# eda.net
KiCad netlist of a schematic drawn in EasyEDA Pro
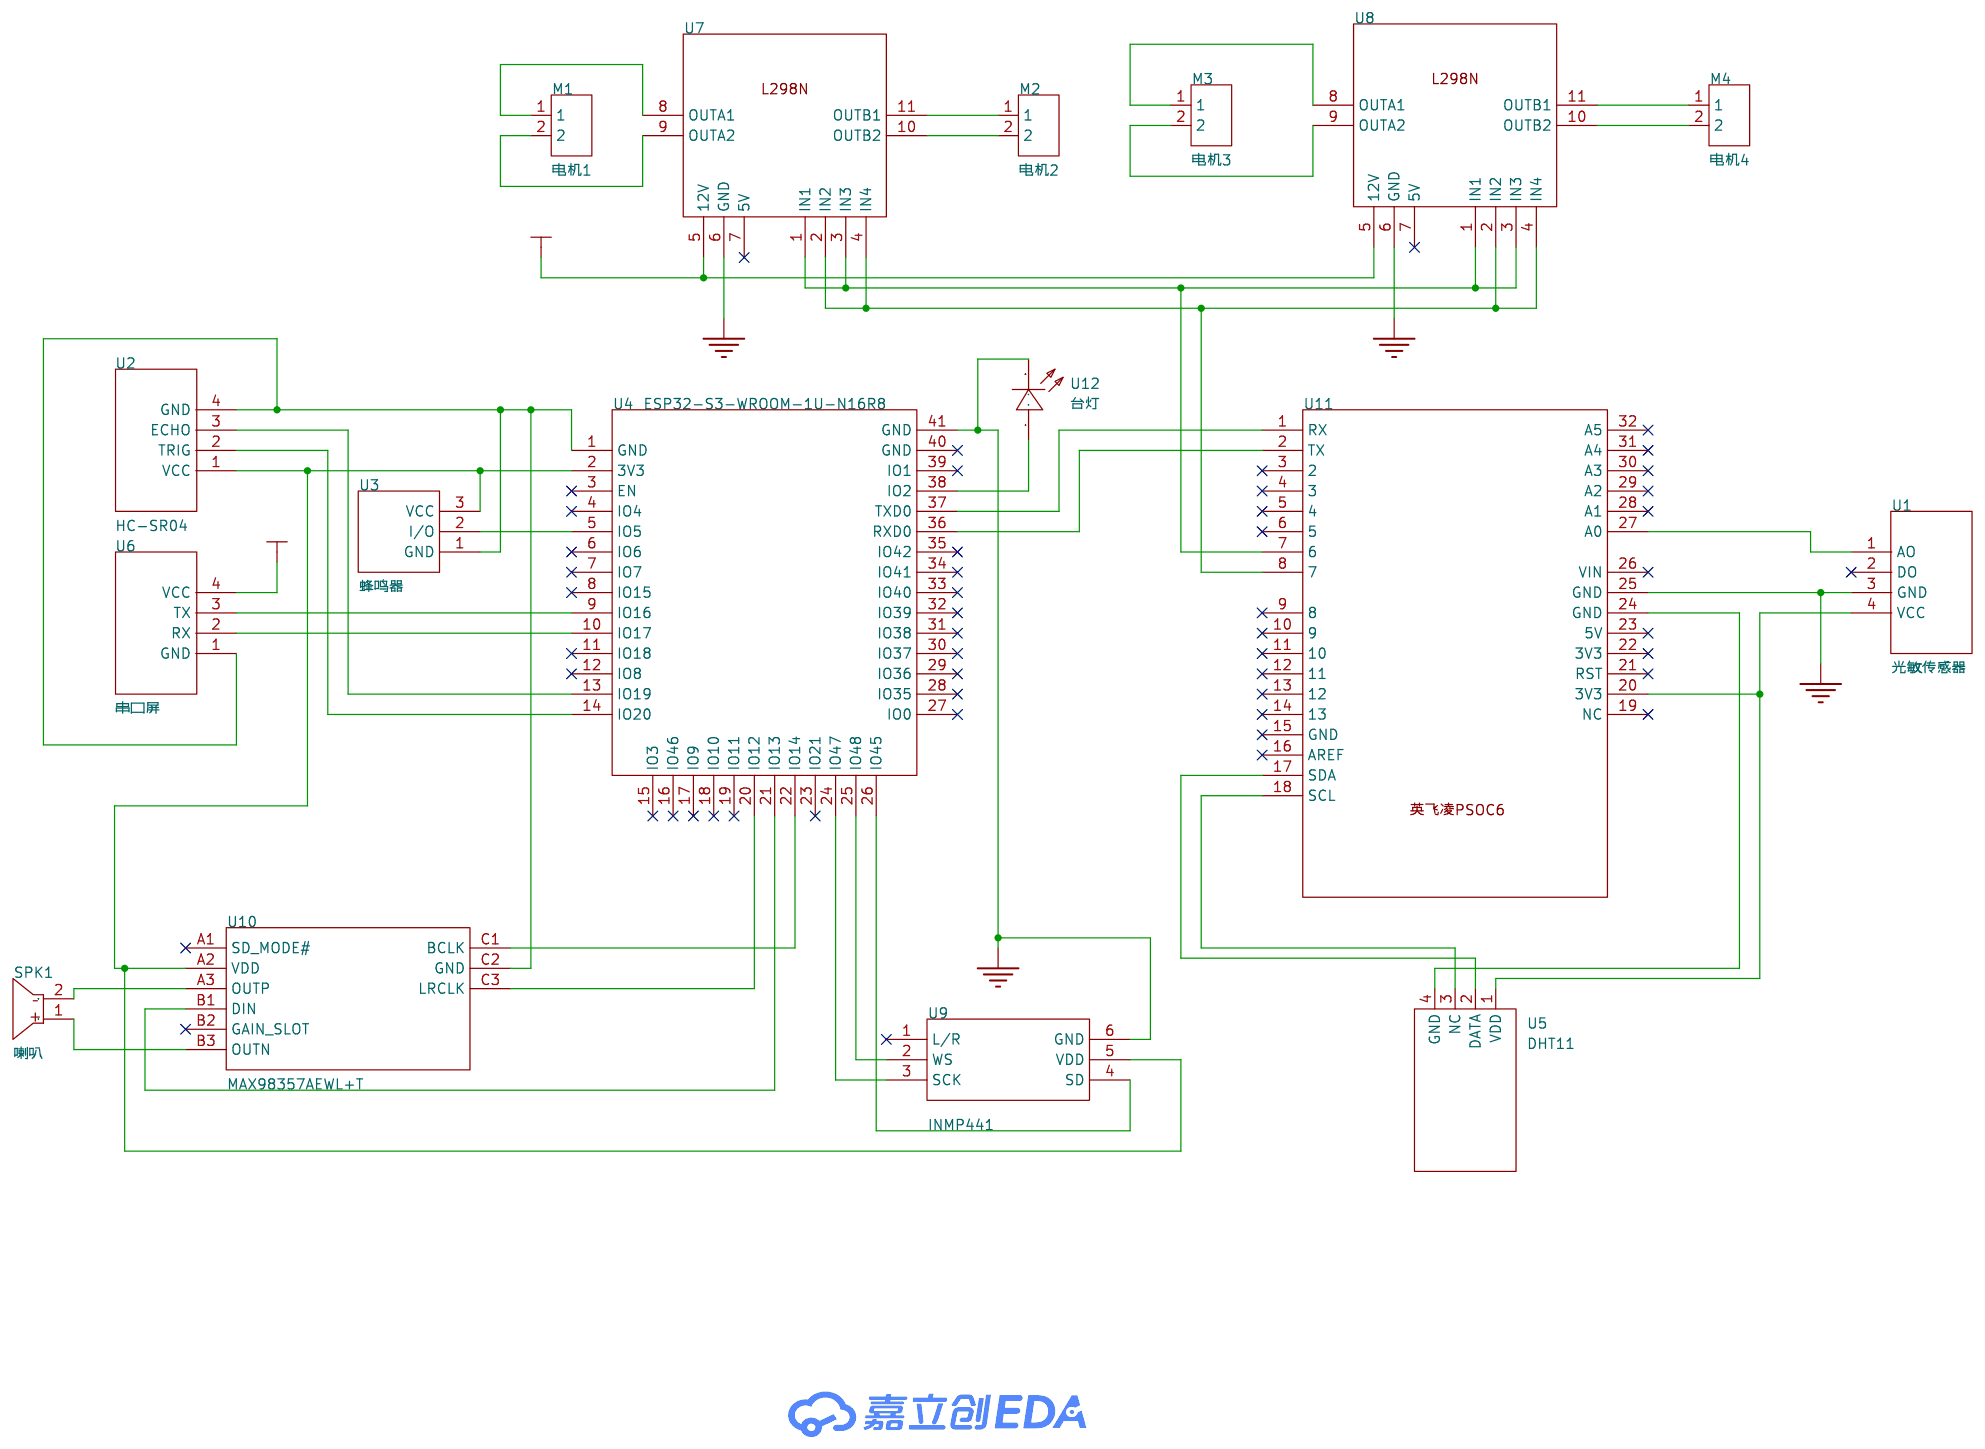
[diagram p0: schematic sheet]

(export (version "E")
  (design (tool "Eeschema 10.0.6"))
  (components
    (comp (ref "M1")
      (value "电机1")
      (footprint "easyedapro:CONN-TH_KF2510-2A")
      (libsource (lib "easyedapro") (part "外接电机-KF2510直针 两个针间距2.54MM"))
    )
    (comp (ref "M2")
      (value "电机2")
      (footprint "easyedapro:CONN-TH_KF2510-2A")
      (libsource (lib "easyedapro") (part "外接电机-KF2510直针 两个针间距2.54MM"))
    )
    (comp (ref "M3")
      (value "电机3")
      (footprint "easyedapro:CONN-TH_KF2510-2A")
      (libsource (lib "easyedapro") (part "外接电机-KF2510直针 两个针间距2.54MM"))
    )
    (comp (ref "M4")
      (value "电机4")
      (footprint "easyedapro:CONN-TH_KF2510-2A")
      (libsource (lib "easyedapro") (part "外接电机-KF2510直针 两个针间距2.54MM"))
    )
    (comp (ref "SPK1")
      (value "喇叭")
      (footprint "easyedapro:BEEP-TH_BD15.0-P10.20-D1.2")
      (description "插针")
      (fields (field (name "Manufacturer") "FUET(福声科技)"))
      (libsource (lib "easyedapro") (part "FS1508MB0810-H8.0"))
    )
    (comp (ref "U1") (value "光敏传感器") (libsource (lib "easyedapro") (part "光敏传感器")))
    (comp (ref "U2") (value "HC-SR04") (libsource (lib "easyedapro") (part "超声波传感器")))
    (comp (ref "U3") (value "蜂鸣器") (libsource (lib "easyedapro") (part "蜂鸣器模块")))
    (comp (ref "U4")
      (value "ESP32-S3-WROOM-1U-N16R8")
      (footprint "easyedapro:WIRELM-SMD_ESP32-S3-WROOM-1U")
      (fields (field (name "Manufacturer") "ESPRESSIF(乐鑫)"))
      (libsource (lib "easyedapro") (part "ESP32-S3-WROOM-1U-N16R8"))
    )
    (comp (ref "U5")
      (value "DHT11")
      (footprint "easyedapro:SENSOR-TH_DHT11")
      (description "新款电容式数字温湿度传感器,老款已停产16.1x12.6x5.8mm")
      (fields (field (name "Manufacturer") "广州奥松"))
      (libsource (lib "easyedapro") (part "DHT11"))
    )
    (comp (ref "U6") (value "串口屏") (libsource (lib "easyedapro") (part "陶晶驰串口屏")))
    (comp (ref "U7") (value "~") (libsource (lib "easyedapro") (part "L298N")))
    (comp (ref "U8") (value "~") (libsource (lib "easyedapro") (part "L298N")))
    (comp (ref "U9") (value "INMP441") (libsource (lib "easyedapro") (part "INMP411")))
    (comp (ref "U10")
      (value "MAX98357AEWL+T")
      (footprint "easyedapro:WLP-9_L1.4-W1.3-P0.40-R3-C3-BR")
      (description "功放类型:-;扬声器通道数:单声道；双声道;输出功率:-;静态电流(Iq):-;")
      (fields (field (name "Manufacturer") "ADI(亚德诺)/MAXIM(美信)"))
      (libsource (lib "easyedapro") (part "MAX98357AEWL+T"))
    )
    (comp (ref "U11") (value "~") (libsource (lib "easyedapro") (part "PSOC6")))
    (comp (ref "U12")
      (value "台灯")
      (footprint "easyedapro:LED0603-R-RD_BLUE")
      (libsource (lib "easyedapro") (part "LED灯,0603,蓝色"))
    )
  )
  (nets
    (net (code "1") (name "5V") (class "Default")
      (node (ref "U6") (pin "4") (pinfunction "VCC_4") (pintype "input"))
    )
    (net (code "2") (name "12V") (class "Default")
      (node (ref "U7") (pin "5") (pinfunction "12V_5") (pintype "input"))
      (node (ref "U8") (pin "5") (pinfunction "12V_5") (pintype "input"))
    )
    (net (code "3") (name "GND") (class "Default")
      (node (ref "U1") (pin "3") (pinfunction "GND_3") (pintype "input"))
      (node (ref "U11") (pin "25") (pinfunction "GND_25") (pintype "input"))
      (node (ref "U12") (pin "2") (pinfunction "K_2") (pintype "unspecified"))
      (node (ref "U4") (pin "41") (pinfunction "GND_41") (pintype "unspecified"))
      (node (ref "U7") (pin "6") (pinfunction "GND_6") (pintype "input"))
      (node (ref "U8") (pin "6") (pinfunction "GND_6") (pintype "input"))
      (node (ref "U9") (pin "6") (pinfunction "GND_6") (pintype "input"))
    )
    (net (code "4") (name "Net-(U1-AO)") (class "Default")
      (node (ref "U1") (pin "1") (pinfunction "AO_1") (pintype "input"))
      (node (ref "U11") (pin "27") (pinfunction "A0_27") (pintype "input"))
    )
    (net (code "5") (name "Net-(U1-VCC)") (class "Default")
      (node (ref "U1") (pin "4") (pinfunction "VCC_4") (pintype "input"))
      (node (ref "U11") (pin "20") (pinfunction "3V3_20") (pintype "input"))
      (node (ref "U5") (pin "1") (pinfunction "VDD_1") (pintype "unspecified"))
    )
    (net (code "6") (name "Net-(U2-ECHO)") (class "Default")
      (node (ref "U2") (pin "3") (pinfunction "ECHO_3") (pintype "input"))
      (node (ref "U4") (pin "13") (pinfunction "IO19_13") (pintype "unspecified"))
    )
    (net (code "7") (name "Net-(U2-TRIG)") (class "Default")
      (node (ref "U2") (pin "2") (pinfunction "TRIG_2") (pintype "input"))
      (node (ref "U4") (pin "14") (pinfunction "IO20_14") (pintype "unspecified"))
    )
    (net (code "8") (name "Net-(U3-I{slash}O)") (class "Default")
      (node (ref "U3") (pin "2") (pinfunction "I/O_2") (pintype "input"))
      (node (ref "U4") (pin "5") (pinfunction "IO5_5") (pintype "unspecified"))
    )
    (net (code "9") (name "Net-(U4-IO16)") (class "Default")
      (node (ref "U4") (pin "9") (pinfunction "IO16_9") (pintype "unspecified"))
      (node (ref "U6") (pin "3") (pinfunction "TX_3") (pintype "input"))
    )
    (net (code "10") (name "Net-(U4-IO17)") (class "Default")
      (node (ref "U4") (pin "10") (pinfunction "IO17_10") (pintype "unspecified"))
      (node (ref "U6") (pin "2") (pinfunction "RX_2") (pintype "input"))
    )
    (net (code "11") (name "Net-(U4-IO45)") (class "Default")
      (node (ref "U4") (pin "26") (pinfunction "IO45_26") (pintype "unspecified"))
      (node (ref "U9") (pin "4") (pinfunction "SD_4") (pintype "input"))
    )
    (net (code "12") (name "Net-(U4-IO47)") (class "Default")
      (node (ref "U4") (pin "24") (pinfunction "IO47_24") (pintype "unspecified"))
      (node (ref "U9") (pin "3") (pinfunction "SCK_3") (pintype "input"))
    )
    (net (code "13") (name "Net-(U4-IO48)") (class "Default")
      (node (ref "U4") (pin "25") (pinfunction "IO48_25") (pintype "unspecified"))
      (node (ref "U9") (pin "2") (pinfunction "WS_2") (pintype "input"))
    )
    (net (code "14") (name "Net-(U5-GND)") (class "Default")
      (node (ref "U11") (pin "24") (pinfunction "GND_24") (pintype "input"))
      (node (ref "U5") (pin "4") (pinfunction "GND_4") (pintype "unspecified"))
    )
    (net (code "15") (name "Net-(U7-OUTA1)") (class "Default")
      (node (ref "M1") (pin "1") (pinfunction "1_1") (pintype "unspecified"))
      (node (ref "U7") (pin "8") (pinfunction "OUTA1_8") (pintype "input"))
    )
    (net (code "16") (name "Net-(U7-OUTA2)") (class "Default")
      (node (ref "M1") (pin "2") (pinfunction "2_2") (pintype "unspecified"))
      (node (ref "U7") (pin "9") (pinfunction "OUTA2_9") (pintype "input"))
    )
    (net (code "17") (name "Net-(U7-OUTB1)") (class "Default")
      (node (ref "M2") (pin "1") (pinfunction "1_1") (pintype "unspecified"))
      (node (ref "U7") (pin "11") (pinfunction "OUTB1_11") (pintype "input"))
    )
    (net (code "18") (name "Net-(U7-OUTB2)") (class "Default")
      (node (ref "M2") (pin "2") (pinfunction "2_2") (pintype "unspecified"))
      (node (ref "U7") (pin "10") (pinfunction "OUTB2_10") (pintype "input"))
    )
    (net (code "19") (name "Net-(U8-OUTA1)") (class "Default")
      (node (ref "M3") (pin "1") (pinfunction "1_1") (pintype "unspecified"))
      (node (ref "U8") (pin "8") (pinfunction "OUTA1_8") (pintype "input"))
    )
    (net (code "20") (name "Net-(U8-OUTA2)") (class "Default")
      (node (ref "M3") (pin "2") (pinfunction "2_2") (pintype "unspecified"))
      (node (ref "U8") (pin "9") (pinfunction "OUTA2_9") (pintype "input"))
    )
    (net (code "21") (name "Net-(U8-OUTB1)") (class "Default")
      (node (ref "M4") (pin "1") (pinfunction "1_1") (pintype "unspecified"))
      (node (ref "U8") (pin "11") (pinfunction "OUTB1_11") (pintype "input"))
    )
    (net (code "22") (name "Net-(U8-OUTB2)") (class "Default")
      (node (ref "M4") (pin "2") (pinfunction "2_2") (pintype "unspecified"))
      (node (ref "U8") (pin "10") (pinfunction "OUTB2_10") (pintype "input"))
    )
    (net (code "23") (name "Net-(U10-BCLK)") (class "Default")
      (node (ref "U10") (pin "C1") (pinfunction "BCLK_C1") (pintype "unspecified"))
      (node (ref "U4") (pin "22") (pinfunction "IO14_22") (pintype "unspecified"))
    )
    (net (code "24") (name "Net-(U10-DIN)") (class "Default")
      (node (ref "U10") (pin "B1") (pinfunction "DIN_B1") (pintype "unspecified"))
      (node (ref "U4") (pin "21") (pinfunction "IO13_21") (pintype "unspecified"))
    )
    (net (code "25") (name "Net-(U10-GND)") (class "Default")
      (node (ref "U10") (pin "C2") (pinfunction "GND_C2") (pintype "unspecified"))
      (node (ref "U2") (pin "4") (pinfunction "GND_4") (pintype "input"))
      (node (ref "U3") (pin "1") (pinfunction "GND_1") (pintype "input"))
      (node (ref "U4") (pin "1") (pinfunction "GND_1") (pintype "unspecified"))
      (node (ref "U6") (pin "1") (pinfunction "GND_1") (pintype "input"))
    )
    (net (code "26") (name "Net-(U10-LRCLK)") (class "Default")
      (node (ref "U10") (pin "C3") (pinfunction "LRCLK_C3") (pintype "unspecified"))
      (node (ref "U4") (pin "20") (pinfunction "IO12_20") (pintype "unspecified"))
    )
    (net (code "27") (name "Net-(U10-OUTN)") (class "Default")
      (node (ref "SPK1") (pin "1") (pinfunction "1_1") (pintype "unspecified"))
      (node (ref "U10") (pin "B3") (pinfunction "OUTN_B3") (pintype "unspecified"))
    )
    (net (code "28") (name "Net-(U10-OUTP)") (class "Default")
      (node (ref "SPK1") (pin "2") (pinfunction "2_2") (pintype "unspecified"))
      (node (ref "U10") (pin "A3") (pinfunction "OUTP_A3") (pintype "unspecified"))
    )
    (net (code "29") (name "Net-(U10-VDD)") (class "Default")
      (node (ref "U10") (pin "A2") (pinfunction "VDD_A2") (pintype "unspecified"))
      (node (ref "U2") (pin "1") (pinfunction "VCC_1") (pintype "input"))
      (node (ref "U3") (pin "3") (pinfunction "VCC_3") (pintype "input"))
      (node (ref "U4") (pin "2") (pinfunction "3V3_2") (pintype "unspecified"))
      (node (ref "U9") (pin "5") (pinfunction "VDD_5") (pintype "input"))
    )
    (net (code "30") (name "Net-(U11-6)") (class "Default")
      (node (ref "U11") (pin "7") (pinfunction "6_7") (pintype "input"))
      (node (ref "U7") (pin "1") (pinfunction "IN1_1") (pintype "input"))
      (node (ref "U7") (pin "3") (pinfunction "IN3_3") (pintype "input"))
      (node (ref "U8") (pin "1") (pinfunction "IN1_1") (pintype "input"))
      (node (ref "U8") (pin "3") (pinfunction "IN3_3") (pintype "input"))
    )
    (net (code "31") (name "Net-(U11-7)") (class "Default")
      (node (ref "U11") (pin "8") (pinfunction "7_8") (pintype "input"))
      (node (ref "U7") (pin "2") (pinfunction "IN2_2") (pintype "input"))
      (node (ref "U7") (pin "4") (pinfunction "IN4_4") (pintype "input"))
      (node (ref "U8") (pin "2") (pinfunction "IN2_2") (pintype "input"))
      (node (ref "U8") (pin "4") (pinfunction "IN4_4") (pintype "input"))
    )
    (net (code "32") (name "Net-(U11-RX)") (class "Default")
      (node (ref "U11") (pin "1") (pinfunction "RX_1") (pintype "input"))
      (node (ref "U4") (pin "37") (pinfunction "TXD0_37") (pintype "unspecified"))
    )
    (net (code "33") (name "Net-(U11-SCL)") (class "Default")
      (node (ref "U11") (pin "18") (pinfunction "SCL_18") (pintype "input"))
      (node (ref "U5") (pin "3") (pinfunction "NC_3") (pintype "unspecified"))
    )
    (net (code "34") (name "Net-(U11-SDA)") (class "Default")
      (node (ref "U11") (pin "17") (pinfunction "SDA_17") (pintype "input"))
      (node (ref "U5") (pin "2") (pinfunction "DATA_2") (pintype "unspecified"))
    )
    (net (code "35") (name "Net-(U11-TX)") (class "Default")
      (node (ref "U11") (pin "2") (pinfunction "TX_2") (pintype "input"))
      (node (ref "U4") (pin "36") (pinfunction "RXD0_36") (pintype "unspecified"))
    )
    (net (code "36") (name "Net-(U12-A)") (class "Default")
      (node (ref "U12") (pin "1") (pinfunction "A_1") (pintype "unspecified"))
      (node (ref "U4") (pin "38") (pinfunction "IO2_38") (pintype "unspecified"))
    )
    (net (code "37") (name "unconnected-(U1-DO-Pad2)") (class "Default")
      (node (ref "U1") (pin "2") (pinfunction "DO_2") (pintype "input+no_connect"))
    )
    (net (code "38") (name "unconnected-(U4-EN-Pad3)") (class "Default")
      (node (ref "U4") (pin "3") (pinfunction "EN_3") (pintype "unspecified+no_connect"))
    )
    (net (code "39") (name "unconnected-(U4-GND-Pad40)") (class "Default")
      (node (ref "U4") (pin "40") (pinfunction "GND_40") (pintype "unspecified+no_connect"))
    )
    (net (code "40") (name "unconnected-(U4-IO0-Pad27)") (class "Default")
      (node (ref "U4") (pin "27") (pinfunction "IO0_27") (pintype "unspecified+no_connect"))
    )
    (net (code "41") (name "unconnected-(U4-IO1-Pad39)") (class "Default")
      (node (ref "U4") (pin "39") (pinfunction "IO1_39") (pintype "unspecified+no_connect"))
    )
    (net (code "42") (name "unconnected-(U4-IO3-Pad15)") (class "Default")
      (node (ref "U4") (pin "15") (pinfunction "IO3_15") (pintype "unspecified+no_connect"))
    )
    (net (code "43") (name "unconnected-(U4-IO4-Pad4)") (class "Default")
      (node (ref "U4") (pin "4") (pinfunction "IO4_4") (pintype "unspecified+no_connect"))
    )
    (net (code "44") (name "unconnected-(U4-IO6-Pad6)") (class "Default")
      (node (ref "U4") (pin "6") (pinfunction "IO6_6") (pintype "unspecified+no_connect"))
    )
    (net (code "45") (name "unconnected-(U4-IO7-Pad7)") (class "Default")
      (node (ref "U4") (pin "7") (pinfunction "IO7_7") (pintype "unspecified+no_connect"))
    )
    (net (code "46") (name "unconnected-(U4-IO8-Pad12)") (class "Default")
      (node (ref "U4") (pin "12") (pinfunction "IO8_12") (pintype "unspecified+no_connect"))
    )
    (net (code "47") (name "unconnected-(U4-IO9-Pad17)") (class "Default")
      (node (ref "U4") (pin "17") (pinfunction "IO9_17") (pintype "unspecified+no_connect"))
    )
    (net (code "48") (name "unconnected-(U4-IO10-Pad18)") (class "Default")
      (node (ref "U4") (pin "18") (pinfunction "IO10_18") (pintype "unspecified+no_connect"))
    )
    (net (code "49") (name "unconnected-(U4-IO11-Pad19)") (class "Default")
      (node (ref "U4") (pin "19") (pinfunction "IO11_19") (pintype "unspecified+no_connect"))
    )
    (net (code "50") (name "unconnected-(U4-IO15-Pad8)") (class "Default")
      (node (ref "U4") (pin "8") (pinfunction "IO15_8") (pintype "unspecified+no_connect"))
    )
    (net (code "51") (name "unconnected-(U4-IO18-Pad11)") (class "Default")
      (node (ref "U4") (pin "11") (pinfunction "IO18_11") (pintype "unspecified+no_connect"))
    )
    (net (code "52") (name "unconnected-(U4-IO21-Pad23)") (class "Default")
      (node (ref "U4") (pin "23") (pinfunction "IO21_23") (pintype "unspecified+no_connect"))
    )
    (net (code "53") (name "unconnected-(U4-IO35-Pad28)") (class "Default")
      (node (ref "U4") (pin "28") (pinfunction "IO35_28") (pintype "unspecified+no_connect"))
    )
    (net (code "54") (name "unconnected-(U4-IO36-Pad29)") (class "Default")
      (node (ref "U4") (pin "29") (pinfunction "IO36_29") (pintype "unspecified+no_connect"))
    )
    (net (code "55") (name "unconnected-(U4-IO37-Pad30)") (class "Default")
      (node (ref "U4") (pin "30") (pinfunction "IO37_30") (pintype "unspecified+no_connect"))
    )
    (net (code "56") (name "unconnected-(U4-IO38-Pad31)") (class "Default")
      (node (ref "U4") (pin "31") (pinfunction "IO38_31") (pintype "unspecified+no_connect"))
    )
    (net (code "57") (name "unconnected-(U4-IO39-Pad32)") (class "Default")
      (node (ref "U4") (pin "32") (pinfunction "IO39_32") (pintype "unspecified+no_connect"))
    )
    (net (code "58") (name "unconnected-(U4-IO40-Pad33)") (class "Default")
      (node (ref "U4") (pin "33") (pinfunction "IO40_33") (pintype "unspecified+no_connect"))
    )
    (net (code "59") (name "unconnected-(U4-IO41-Pad34)") (class "Default")
      (node (ref "U4") (pin "34") (pinfunction "IO41_34") (pintype "unspecified+no_connect"))
    )
    (net (code "60") (name "unconnected-(U4-IO42-Pad35)") (class "Default")
      (node (ref "U4") (pin "35") (pinfunction "IO42_35") (pintype "unspecified+no_connect"))
    )
    (net (code "61") (name "unconnected-(U4-IO46-Pad16)") (class "Default")
      (node (ref "U4") (pin "16") (pinfunction "IO46_16") (pintype "unspecified+no_connect"))
    )
    (net (code "62") (name "unconnected-(U7-5V-Pad7)") (class "Default")
      (node (ref "U7") (pin "7") (pinfunction "5V_7") (pintype "input+no_connect"))
    )
    (net (code "63") (name "unconnected-(U8-5V-Pad7)") (class "Default")
      (node (ref "U8") (pin "7") (pinfunction "5V_7") (pintype "input+no_connect"))
    )
    (net (code "64") (name "unconnected-(U9-L{slash}R-Pad1)") (class "Default")
      (node (ref "U9") (pin "1") (pinfunction "L/R_1") (pintype "input+no_connect"))
    )
    (net (code "65") (name "unconnected-(U10-GAIN_SLOT-PadB2)") (class "Default")
      (node (ref "U10") (pin "B2") (pinfunction "GAIN_SLOT_B2") (pintype "unspecified+no_connect"))
    )
    (net (code "66") (name "unconnected-(U10-SD_MODE#-PadA1)") (class "Default")
      (node (ref "U10") (pin "A1") (pinfunction "SD_MODE#_A1") (pintype "unspecified+no_connect"))
    )
    (net (code "67") (name "unconnected-(U11-2-Pad3)") (class "Default")
      (node (ref "U11") (pin "3") (pinfunction "2_3") (pintype "input+no_connect"))
    )
    (net (code "68") (name "unconnected-(U11-3-Pad4)") (class "Default")
      (node (ref "U11") (pin "4") (pinfunction "3_4") (pintype "input+no_connect"))
    )
    (net (code "69") (name "unconnected-(U11-3V3-Pad22)") (class "Default")
      (node (ref "U11") (pin "22") (pinfunction "3V3_22") (pintype "input+no_connect"))
    )
    (net (code "70") (name "unconnected-(U11-4-Pad5)") (class "Default")
      (node (ref "U11") (pin "5") (pinfunction "4_5") (pintype "input+no_connect"))
    )
    (net (code "71") (name "unconnected-(U11-5-Pad6)") (class "Default")
      (node (ref "U11") (pin "6") (pinfunction "5_6") (pintype "input+no_connect"))
    )
    (net (code "72") (name "unconnected-(U11-5V-Pad23)") (class "Default")
      (node (ref "U11") (pin "23") (pinfunction "5V_23") (pintype "input+no_connect"))
    )
    (net (code "73") (name "unconnected-(U11-8-Pad9)") (class "Default")
      (node (ref "U11") (pin "9") (pinfunction "8_9") (pintype "input+no_connect"))
    )
    (net (code "74") (name "unconnected-(U11-9-Pad10)") (class "Default")
      (node (ref "U11") (pin "10") (pinfunction "9_10") (pintype "input+no_connect"))
    )
    (net (code "75") (name "unconnected-(U11-10-Pad11)") (class "Default")
      (node (ref "U11") (pin "11") (pinfunction "10_11") (pintype "input+no_connect"))
    )
    (net (code "76") (name "unconnected-(U11-11-Pad12)") (class "Default")
      (node (ref "U11") (pin "12") (pinfunction "11_12") (pintype "input+no_connect"))
    )
    (net (code "77") (name "unconnected-(U11-12-Pad13)") (class "Default")
      (node (ref "U11") (pin "13") (pinfunction "12_13") (pintype "input+no_connect"))
    )
    (net (code "78") (name "unconnected-(U11-13-Pad14)") (class "Default")
      (node (ref "U11") (pin "14") (pinfunction "13_14") (pintype "input+no_connect"))
    )
    (net (code "79") (name "unconnected-(U11-A1-Pad28)") (class "Default")
      (node (ref "U11") (pin "28") (pinfunction "A1_28") (pintype "input+no_connect"))
    )
    (net (code "80") (name "unconnected-(U11-A2-Pad29)") (class "Default")
      (node (ref "U11") (pin "29") (pinfunction "A2_29") (pintype "input+no_connect"))
    )
    (net (code "81") (name "unconnected-(U11-A3-Pad30)") (class "Default")
      (node (ref "U11") (pin "30") (pinfunction "A3_30") (pintype "input+no_connect"))
    )
    (net (code "82") (name "unconnected-(U11-A4-Pad31)") (class "Default")
      (node (ref "U11") (pin "31") (pinfunction "A4_31") (pintype "input+no_connect"))
    )
    (net (code "83") (name "unconnected-(U11-A5-Pad32)") (class "Default")
      (node (ref "U11") (pin "32") (pinfunction "A5_32") (pintype "input+no_connect"))
    )
    (net (code "84") (name "unconnected-(U11-AREF-Pad16)") (class "Default")
      (node (ref "U11") (pin "16") (pinfunction "AREF_16") (pintype "input+no_connect"))
    )
    (net (code "85") (name "unconnected-(U11-GND-Pad15)") (class "Default")
      (node (ref "U11") (pin "15") (pinfunction "GND_15") (pintype "input+no_connect"))
    )
    (net (code "86") (name "unconnected-(U11-NC-Pad19)") (class "Default")
      (node (ref "U11") (pin "19") (pinfunction "NC_19") (pintype "input+no_connect"))
    )
    (net (code "87") (name "unconnected-(U11-RST-Pad21)") (class "Default")
      (node (ref "U11") (pin "21") (pinfunction "RST_21") (pintype "input+no_connect"))
    )
    (net (code "88") (name "unconnected-(U11-VIN-Pad26)") (class "Default")
      (node (ref "U11") (pin "26") (pinfunction "VIN_26") (pintype "input+no_connect"))
    )
  )
)
